# PT8211_T3_0_1.net
KiCad netlist of a schematic drawn in EAGLE
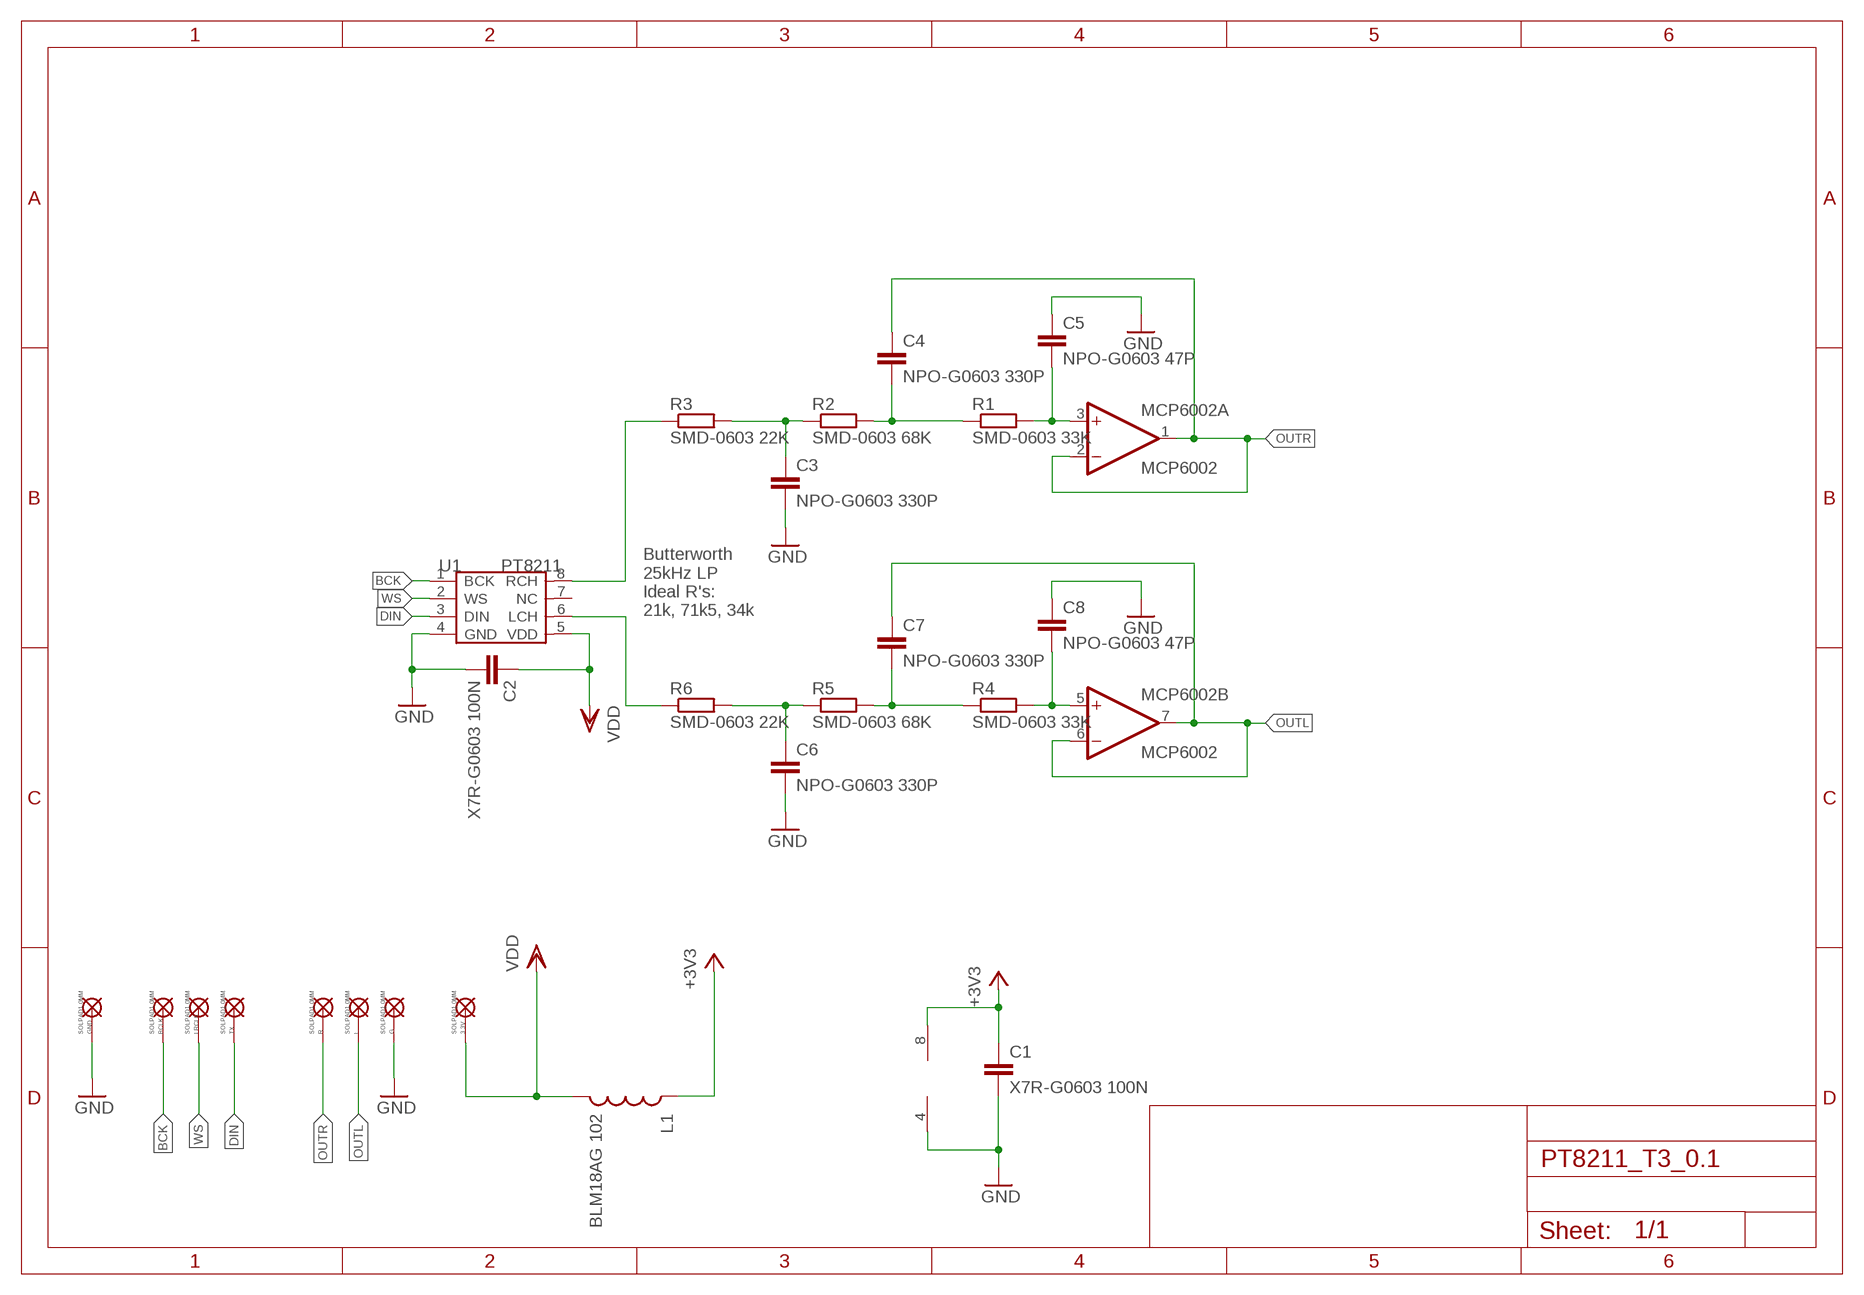
[diagram p0: schematic, sheet 1]

(export (version "E")
  (design (tool "Eeschema 10.0.6"))
  (components
    (comp (ref "3.3V")
      (value "SOLPAD1,0MM")
      (footprint "eagle-import:SOLPAD1MM")
      (libsource (lib "eagle-import") (part "SOLPAD1,0MM"))
    )
    (comp (ref "BCLK")
      (value "SOLPAD1,0MM")
      (footprint "eagle-import:SOLPAD1MM")
      (libsource (lib "eagle-import") (part "SOLPAD1,0MM"))
    )
    (comp (ref "C1")
      (value "X7R-G0603 100N")
      (footprint "eagle-import:C0603K")
      (libsource (lib "eagle-import") (part "C-EUC0603K"))
    )
    (comp (ref "C2")
      (value "X7R-G0603 100N")
      (footprint "eagle-import:C0603K")
      (libsource (lib "eagle-import") (part "C-EUC0603K"))
    )
    (comp (ref "C3")
      (value "NPO-G0603 330P")
      (footprint "eagle-import:C0603K")
      (libsource (lib "eagle-import") (part "C-EUC0603K"))
    )
    (comp (ref "C4")
      (value "NPO-G0603 330P")
      (footprint "eagle-import:C0603K")
      (libsource (lib "eagle-import") (part "C-EUC0603K"))
    )
    (comp (ref "C5")
      (value "NPO-G0603 47P")
      (footprint "eagle-import:C0603K")
      (libsource (lib "eagle-import") (part "C-EUC0603K"))
    )
    (comp (ref "C6")
      (value "NPO-G0603 330P")
      (footprint "eagle-import:C0603K")
      (libsource (lib "eagle-import") (part "C-EUC0603K"))
    )
    (comp (ref "C7")
      (value "NPO-G0603 330P")
      (footprint "eagle-import:C0603K")
      (libsource (lib "eagle-import") (part "C-EUC0603K"))
    )
    (comp (ref "C8")
      (value "NPO-G0603 47P")
      (footprint "eagle-import:C0603K")
      (libsource (lib "eagle-import") (part "C-EUC0603K"))
    )
    (comp (ref "G")
      (value "SOLPAD1,0MM")
      (footprint "eagle-import:SOLPAD1MM")
      (libsource (lib "eagle-import") (part "SOLPAD1,0MM"))
    )
    (comp (ref "GND")
      (value "SOLPAD1,0MM")
      (footprint "eagle-import:SOLPAD1MM")
      (libsource (lib "eagle-import") (part "SOLPAD1,0MM"))
    )
    (comp (ref "L")
      (value "SOLPAD1,0MM")
      (footprint "eagle-import:SOLPAD1MM")
      (libsource (lib "eagle-import") (part "SOLPAD1,0MM"))
    )
    (comp (ref "L1")
      (value "BLM18AG 102")
      (footprint "eagle-import:0603")
      (libsource (lib "eagle-import") (part "INDUCTOR0603"))
    )
    (comp (ref "LRCLK")
      (value "SOLPAD1,0MM")
      (footprint "eagle-import:SOLPAD1MM")
      (libsource (lib "eagle-import") (part "SOLPAD1,0MM"))
    )
    (comp (ref "MCP6002")
      (value "MCP6002")
      (footprint "eagle-import:SO08")
      (libsource (lib "eagle-import") (part "MCP602SN"))
    )
    (comp (ref "R")
      (value "SOLPAD1,0MM")
      (footprint "eagle-import:SOLPAD1MM")
      (libsource (lib "eagle-import") (part "SOLPAD1,0MM"))
    )
    (comp (ref "R1")
      (value "SMD-0603 33K")
      (footprint "eagle-import:R0603")
      (libsource (lib "eagle-import") (part "R-EU_R0603"))
    )
    (comp (ref "R2")
      (value "SMD-0603 68K")
      (footprint "eagle-import:R0603")
      (libsource (lib "eagle-import") (part "R-EU_R0603"))
    )
    (comp (ref "R3")
      (value "SMD-0603 22K")
      (footprint "eagle-import:R0603")
      (libsource (lib "eagle-import") (part "R-EU_R0603"))
    )
    (comp (ref "R4")
      (value "SMD-0603 33K")
      (footprint "eagle-import:R0603")
      (libsource (lib "eagle-import") (part "R-EU_R0603"))
    )
    (comp (ref "R5")
      (value "SMD-0603 68K")
      (footprint "eagle-import:R0603")
      (libsource (lib "eagle-import") (part "R-EU_R0603"))
    )
    (comp (ref "R6")
      (value "SMD-0603 22K")
      (footprint "eagle-import:R0603")
      (libsource (lib "eagle-import") (part "R-EU_R0603"))
    )
    (comp (ref "TX")
      (value "SOLPAD1,0MM")
      (footprint "eagle-import:SOLPAD1MM")
      (libsource (lib "eagle-import") (part "SOLPAD1,0MM"))
    )
    (comp (ref "U1")
      (value "PT8211")
      (footprint "eagle-import:SOP8-6.0-4.9X3.9")
      (libsource (lib "eagle-import") (part "PT8211-SOP8"))
    )
  )
  (nets
    (net (code "1") (name "+3V3") (class "Default")
      (node (ref "C1") (pin "1") (pinfunction "1_1") (pintype "passive"))
      (node (ref "L1") (pin "1") (pinfunction "1_1") (pintype "passive"))
      (node (ref "MCP6002") (pin "8") (pinfunction "V+_8") (pintype "power_in"))
    )
    (net (code "2") (name "BCK") (class "Default")
      (node (ref "BCLK") (pin "P$1") (pinfunction "P$1_P$1") (pintype "bidirectional"))
      (node (ref "U1") (pin "1") (pinfunction "BCK_1") (pintype "input"))
    )
    (net (code "3") (name "DIN") (class "Default")
      (node (ref "TX") (pin "P$1") (pinfunction "P$1_P$1") (pintype "bidirectional"))
      (node (ref "U1") (pin "3") (pinfunction "DIN_3") (pintype "input"))
    )
    (net (code "4") (name "GND") (class "Default")
      (node (ref "C1") (pin "2") (pinfunction "2_2") (pintype "passive"))
      (node (ref "C2") (pin "2") (pinfunction "2_2") (pintype "passive"))
      (node (ref "C3") (pin "2") (pinfunction "2_2") (pintype "passive"))
      (node (ref "C5") (pin "1") (pinfunction "1_1") (pintype "passive"))
      (node (ref "C6") (pin "2") (pinfunction "2_2") (pintype "passive"))
      (node (ref "C8") (pin "1") (pinfunction "1_1") (pintype "passive"))
      (node (ref "G") (pin "P$1") (pinfunction "P$1_P$1") (pintype "bidirectional"))
      (node (ref "GND") (pin "P$1") (pinfunction "P$1_P$1") (pintype "bidirectional"))
      (node (ref "MCP6002") (pin "4") (pinfunction "V-_4") (pintype "power_in"))
      (node (ref "U1") (pin "4") (pinfunction "GND_4") (pintype "power_in"))
    )
    (net (code "5") (name "Net-(C3-Pad1)") (class "Default")
      (node (ref "C3") (pin "1") (pinfunction "1_1") (pintype "passive"))
      (node (ref "R2") (pin "1") (pinfunction "1_1") (pintype "passive"))
      (node (ref "R3") (pin "2") (pinfunction "2_2") (pintype "passive"))
    )
    (net (code "6") (name "Net-(C4-Pad2)") (class "Default")
      (node (ref "C4") (pin "2") (pinfunction "2_2") (pintype "passive"))
      (node (ref "R1") (pin "1") (pinfunction "1_1") (pintype "passive"))
      (node (ref "R2") (pin "2") (pinfunction "2_2") (pintype "passive"))
    )
    (net (code "7") (name "Net-(C6-Pad1)") (class "Default")
      (node (ref "C6") (pin "1") (pinfunction "1_1") (pintype "passive"))
      (node (ref "R5") (pin "1") (pinfunction "1_1") (pintype "passive"))
      (node (ref "R6") (pin "2") (pinfunction "2_2") (pintype "passive"))
    )
    (net (code "8") (name "Net-(C7-Pad2)") (class "Default")
      (node (ref "C7") (pin "2") (pinfunction "2_2") (pintype "passive"))
      (node (ref "R4") (pin "1") (pinfunction "1_1") (pintype "passive"))
      (node (ref "R5") (pin "2") (pinfunction "2_2") (pintype "passive"))
    )
    (net (code "9") (name "Net-(MCP6002A-+IN)") (class "Default")
      (node (ref "C5") (pin "2") (pinfunction "2_2") (pintype "passive"))
      (node (ref "MCP6002") (pin "3") (pinfunction "+IN_3") (pintype "input"))
      (node (ref "R1") (pin "2") (pinfunction "2_2") (pintype "passive"))
    )
    (net (code "10") (name "Net-(MCP6002B-+IN)") (class "Default")
      (node (ref "C8") (pin "2") (pinfunction "2_2") (pintype "passive"))
      (node (ref "MCP6002") (pin "5") (pinfunction "+IN_5") (pintype "input"))
      (node (ref "R4") (pin "2") (pinfunction "2_2") (pintype "passive"))
    )
    (net (code "11") (name "Net-(U1-LCH)") (class "Default")
      (node (ref "R6") (pin "1") (pinfunction "1_1") (pintype "passive"))
      (node (ref "U1") (pin "6") (pinfunction "LCH_6") (pintype "output"))
    )
    (net (code "12") (name "Net-(U1-RCH)") (class "Default")
      (node (ref "R3") (pin "1") (pinfunction "1_1") (pintype "passive"))
      (node (ref "U1") (pin "8") (pinfunction "RCH_8") (pintype "output"))
    )
    (net (code "13") (name "OUTL") (class "Default")
      (node (ref "C7") (pin "1") (pinfunction "1_1") (pintype "passive"))
      (node (ref "L") (pin "P$1") (pinfunction "P$1_P$1") (pintype "bidirectional"))
      (node (ref "MCP6002") (pin "6") (pinfunction "-IN_6") (pintype "input"))
      (node (ref "MCP6002") (pin "7") (pinfunction "OUT_7") (pintype "output"))
    )
    (net (code "14") (name "OUTR") (class "Default")
      (node (ref "C4") (pin "1") (pinfunction "1_1") (pintype "passive"))
      (node (ref "MCP6002") (pin "1") (pinfunction "OUT_1") (pintype "output"))
      (node (ref "MCP6002") (pin "2") (pinfunction "-IN_2") (pintype "input"))
      (node (ref "R") (pin "P$1") (pinfunction "P$1_P$1") (pintype "bidirectional"))
    )
    (net (code "15") (name "VDD") (class "Default")
      (node (ref "3.3V") (pin "P$1") (pinfunction "P$1_P$1") (pintype "bidirectional"))
      (node (ref "C2") (pin "1") (pinfunction "1_1") (pintype "passive"))
      (node (ref "L1") (pin "2") (pinfunction "2_2") (pintype "passive"))
      (node (ref "U1") (pin "5") (pinfunction "VDD_5") (pintype "power_in"))
    )
    (net (code "16") (name "WS") (class "Default")
      (node (ref "LRCLK") (pin "P$1") (pinfunction "P$1_P$1") (pintype "bidirectional"))
      (node (ref "U1") (pin "2") (pinfunction "WS_2") (pintype "input"))
    )
    (net (code "17") (name "unconnected-(U1-NC-Pad7)") (class "Default")
      (node (ref "U1") (pin "7") (pinfunction "NC_7") (pintype "no_connect"))
    )
  )
)
